# VCAN.net
KiCad netlist of a schematic drawn in Altium Designer
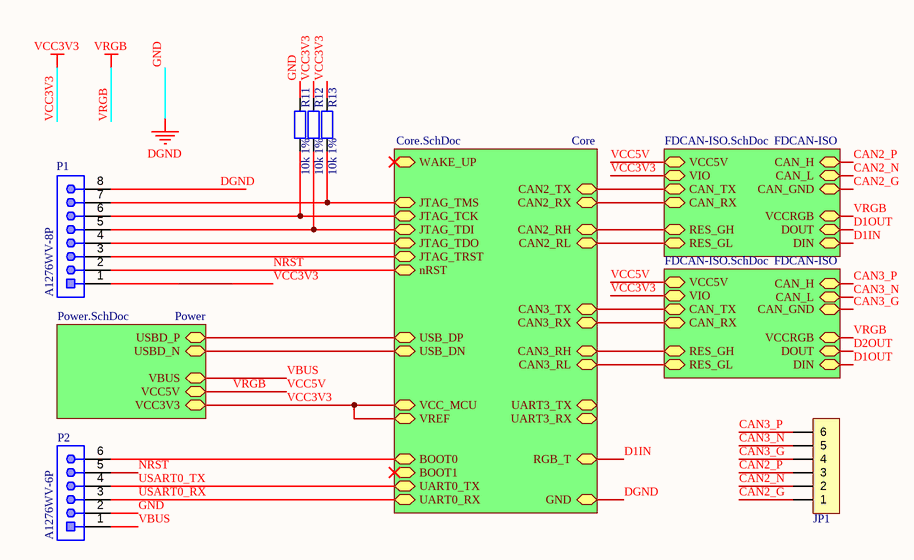
[diagram p0: VCAN.SchDoc]

(export (version "E")
  (design (tool "Eeschema 10.0.6"))
  (components
    (comp (ref "JP1")
      (value "HDR-1X6")
      (footprint "HT3.96-WI-6P-SMD")
      (description "6P接插件")
      (libsource (lib "5.6  - 接插件-脚距3.96") (part "Header 6"))
    )
    (comp (ref "P1")
      (value "A1276WV-8P")
      (footprint "CJT-A1276WV-8P_V")
      (description "Pin Header, 1.27mm Pitch 180° Single Row, 1 x 8 Position, Height 3.7 mm, -40 to 105 degC, RoHS")
      (fields
        (field (name "MANUFACTURER") "Changjiang Connectors")
        (field (name "PUBLISHER") "Bolgen Studio")
      )
      (libsource (lib "14-01. 排针排母") (part "A1276WV-8P"))
    )
    (comp (ref "P2")
      (value "A1276WV-6P")
      (footprint "CJT-A1276WV-6P_V")
      (description "Pin Header, 1.27mm Pitch 180° Single Row, 1 x 6 Position, Height 3.7 mm, -40 to 105 degC, RoHS")
      (fields
        (field (name "MANUFACTURER") "Changjiang Connectors")
        (field (name "PUBLISHER") "Bolgen Studio")
      )
      (libsource (lib "14-01. 排针排母") (part "A1276WV-6P"))
    )
    (comp (ref "R11")
      (value "10k 1%")
      (footprint "R 0603_L")
      (description "贴片电阻")
      (libsource (lib "0.1 - 电阻-电容-电感") (part "R"))
    )
    (comp (ref "R12")
      (value "10k 1%")
      (footprint "R 0603_L")
      (description "贴片电阻")
      (libsource (lib "0.1 - 电阻-电容-电感") (part "R"))
    )
    (comp (ref "R13")
      (value "10k 1%")
      (footprint "R 0603_L")
      (description "贴片电阻")
      (libsource (lib "0.1 - 电阻-电容-电感") (part "R"))
    )
  )
  (nets
    (net (code "1") (name "/BOOT0") (class "Default")
      (node (ref "P2") (pin "6") (pinfunction "6_6") (pintype "passive"))
    )
    (net (code "3") (name "/CAN2_G") (class "Default")
      (node (ref "JP1") (pin "1") (pinfunction "1_1") (pintype "passive"))
    )
    (net (code "4") (name "/CAN2_N") (class "Default")
      (node (ref "JP1") (pin "2") (pinfunction "2_2") (pintype "passive"))
    )
    (net (code "5") (name "/CAN2_P") (class "Default")
      (node (ref "JP1") (pin "3") (pinfunction "3_3") (pintype "passive"))
    )
    (net (code "10") (name "/CAN3_G") (class "Default")
      (node (ref "JP1") (pin "4") (pinfunction "4_4") (pintype "passive"))
    )
    (net (code "11") (name "/CAN3_N") (class "Default")
      (node (ref "JP1") (pin "5") (pinfunction "5_5") (pintype "passive"))
    )
    (net (code "12") (name "/CAN3_P") (class "Default")
      (node (ref "JP1") (pin "6") (pinfunction "6_6") (pintype "passive"))
    )
    (net (code "20") (name "/JTAG_TCK") (class "Default")
      (node (ref "P1") (pin "6") (pinfunction "6_6") (pintype "passive"))
      (node (ref "R11") (pin "2") (pinfunction "2_2") (pintype "passive"))
    )
    (net (code "21") (name "/JTAG_TDI") (class "Default")
      (node (ref "P1") (pin "5") (pinfunction "5_5") (pintype "passive"))
      (node (ref "R12") (pin "2") (pinfunction "2_2") (pintype "passive"))
    )
    (net (code "22") (name "/JTAG_TDO") (class "Default")
      (node (ref "P1") (pin "4") (pinfunction "4_4") (pintype "passive"))
    )
    (net (code "23") (name "/JTAG_TMS") (class "Default")
      (node (ref "P1") (pin "7") (pinfunction "7_7") (pintype "passive"))
      (node (ref "R13") (pin "2") (pinfunction "2_2") (pintype "passive"))
    )
    (net (code "24") (name "/JTAG_TRST") (class "Default")
      (node (ref "P1") (pin "3") (pinfunction "3_3") (pintype "passive"))
    )
    (net (code "25") (name "/NRST") (class "Default")
      (node (ref "P1") (pin "2") (pinfunction "2_2") (pintype "passive"))
      (node (ref "P2") (pin "5") (pinfunction "5_5") (pintype "passive"))
    )
    (net (code "28") (name "/USART0_RX") (class "Default")
      (node (ref "P2") (pin "3") (pinfunction "3_3") (pintype "passive"))
    )
    (net (code "29") (name "/USART0_TX") (class "Default")
      (node (ref "P2") (pin "4") (pinfunction "4_4") (pintype "passive"))
    )
    (net (code "32") (name "/VBUS") (class "Default")
      (node (ref "P2") (pin "1") (pinfunction "1_1") (pintype "passive"))
    )
    (net (code "34") (name "DGND") (class "Default")
      (node (ref "P1") (pin "8") (pinfunction "8_8") (pintype "passive"))
      (node (ref "P2") (pin "2") (pinfunction "2_2") (pintype "passive"))
      (node (ref "R11") (pin "1") (pinfunction "1_1") (pintype "passive"))
    )
    (net (code "35") (name "VCC3V3") (class "Default")
      (node (ref "P1") (pin "1") (pinfunction "1_1") (pintype "passive"))
      (node (ref "R12") (pin "1") (pinfunction "1_1") (pintype "passive"))
      (node (ref "R13") (pin "1") (pinfunction "1_1") (pintype "passive"))
    )
  )
)
